# mainboard.net
KiCad netlist of a schematic drawn in EAGLE
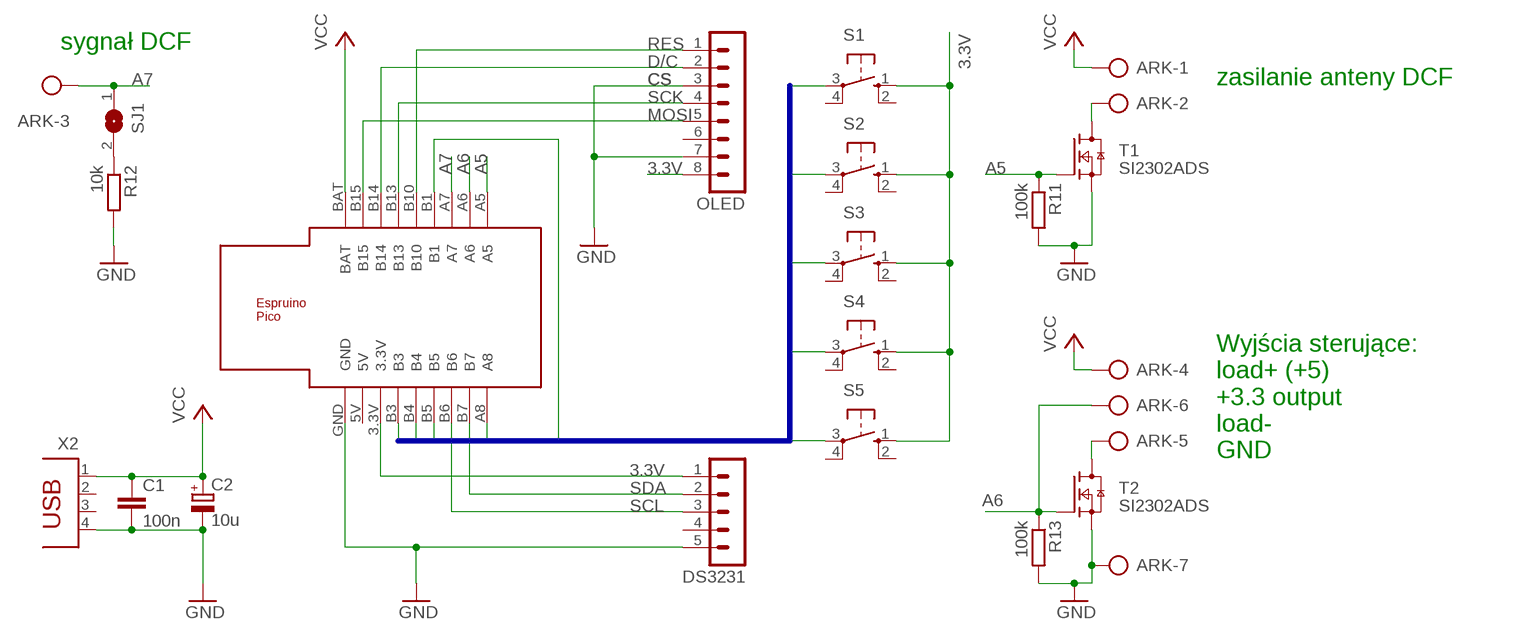
[diagram p0: schematic, sheet 1]

(export (version "E")
  (design (tool "Eeschema 10.0.6"))
  (components
    (comp (ref "ARK")
      (value "AK500/7")
      (footprint "eagle-import:AK500_7")
      (libsource (lib "eagle-import") (part "AK500/7"))
    )
    (comp (ref "C1")
      (value "100n")
      (footprint "eagle-import:C1206K")
      (libsource (lib "eagle-import") (part "C-EUC1206K"))
    )
    (comp (ref "C2")
      (value "10u")
      (footprint "eagle-import:A_3216-18W")
      (libsource (lib "eagle-import") (part "CPOL-EUA/3216-18W"))
    )
    (comp (ref "DS3231")
      (value "MA05-1")
      (footprint "eagle-import:MA05-1")
      (libsource (lib "eagle-import") (part "MA05-1"))
    )
    (comp (ref "OLED")
      (value "MA08-1")
      (footprint "eagle-import:MA08-1")
      (libsource (lib "eagle-import") (part "MA08-1"))
    )
    (comp (ref "R11")
      (value "100k")
      (footprint "eagle-import:M0805")
      (libsource (lib "eagle-import") (part "R-EU_M0805"))
    )
    (comp (ref "R12")
      (value "10k")
      (footprint "eagle-import:M0805")
      (libsource (lib "eagle-import") (part "R-EU_M0805"))
    )
    (comp (ref "R13")
      (value "100k")
      (footprint "eagle-import:M0805")
      (libsource (lib "eagle-import") (part "R-EU_M0805"))
    )
    (comp (ref "S1")
      (value "10-XX")
      (footprint "eagle-import:B3F-10XX")
      (fields (field (name "MPN") "B3F-1000"))
      (libsource (lib "eagle-import") (part "10-XX"))
    )
    (comp (ref "S2")
      (value "10-XX")
      (footprint "eagle-import:B3F-10XX")
      (fields (field (name "MPN") "B3F-1000"))
      (libsource (lib "eagle-import") (part "10-XX"))
    )
    (comp (ref "S3")
      (value "10-XX")
      (footprint "eagle-import:B3F-10XX")
      (fields (field (name "MPN") "B3F-1000"))
      (libsource (lib "eagle-import") (part "10-XX"))
    )
    (comp (ref "S4")
      (value "10-XX")
      (footprint "eagle-import:B3F-10XX")
      (fields (field (name "MPN") "B3F-1000"))
      (libsource (lib "eagle-import") (part "10-XX"))
    )
    (comp (ref "S5")
      (value "10-XX")
      (footprint "eagle-import:B3F-10XX")
      (fields (field (name "MPN") "B3F-1000"))
      (libsource (lib "eagle-import") (part "10-XX"))
    )
    (comp (ref "SJ1") (value "SJ") (footprint "eagle-import:SJ") (libsource (lib "eagle-import") (part "SJ")))
    (comp (ref "T1")
      (value "SI2302ADS")
      (footprint "eagle-import:SOT23")
      (libsource (lib "eagle-import") (part "2N7002E"))
    )
    (comp (ref "T2")
      (value "SI2302ADS")
      (footprint "eagle-import:SOT23")
      (libsource (lib "eagle-import") (part "2N7002E"))
    )
    (comp (ref "U$1")
      (value "ESPRUINO_PICO_0.1")
      (footprint "eagle-import:ESPRUINO_PICO_0.1")
      (libsource (lib "eagle-import") (part "ESPRUINO_PICO_0.1"))
    )
    (comp (ref "X2")
      (value "PN61729")
      (footprint "eagle-import:PN61729")
      (libsource (lib "eagle-import") (part "PN61729"))
    )
  )
  (nets
    (net (code "1") (name "/3.3V") (class "Default")
      (node (ref "DS3231") (pin "1") (pinfunction "1_1") (pintype "passive"))
      (node (ref "OLED") (pin "8") (pinfunction "8_8") (pintype "passive"))
      (node (ref "S1") (pin "1") (pinfunction "S_1") (pintype "passive"))
      (node (ref "S2") (pin "1") (pinfunction "S_1") (pintype "passive"))
      (node (ref "S3") (pin "1") (pinfunction "S_1") (pintype "passive"))
      (node (ref "S4") (pin "1") (pinfunction "S_1") (pintype "passive"))
      (node (ref "S5") (pin "1") (pinfunction "S_1") (pintype "passive"))
      (node (ref "U$1") (pin "3.3V") (pinfunction "3.3V_3.3V") (pintype "bidirectional"))
    )
    (net (code "2") (name "/A5") (class "Default")
      (node (ref "R11") (pin "1") (pinfunction "1_1") (pintype "passive"))
      (node (ref "T1") (pin "1") (pinfunction "G_1") (pintype "passive"))
      (node (ref "U$1") (pin "A5") (pinfunction "A5_A5") (pintype "bidirectional"))
    )
    (net (code "3") (name "/A6") (class "Default")
      (node (ref "ARK") (pin "6") (pinfunction "KL_6") (pintype "passive"))
      (node (ref "R13") (pin "1") (pinfunction "1_1") (pintype "passive"))
      (node (ref "T2") (pin "1") (pinfunction "G_1") (pintype "passive"))
      (node (ref "U$1") (pin "A6") (pinfunction "A6_A6") (pintype "bidirectional"))
    )
    (net (code "4") (name "/A7") (class "Default")
      (node (ref "ARK") (pin "3") (pinfunction "KL_3") (pintype "passive"))
      (node (ref "SJ1") (pin "1") (pinfunction "1_1") (pintype "passive"))
      (node (ref "U$1") (pin "A7") (pinfunction "A7_A7") (pintype "bidirectional"))
    )
    (net (code "5") (name "/D{slash}C") (class "Default")
      (node (ref "OLED") (pin "2") (pinfunction "2_2") (pintype "passive"))
      (node (ref "U$1") (pin "B14") (pinfunction "B14_B14") (pintype "bidirectional"))
    )
    (net (code "6") (name "/MOSI") (class "Default")
      (node (ref "OLED") (pin "5") (pinfunction "5_5") (pintype "passive"))
      (node (ref "U$1") (pin "B15") (pinfunction "B15_B15") (pintype "bidirectional"))
    )
    (net (code "7") (name "/RES") (class "Default")
      (node (ref "OLED") (pin "1") (pinfunction "1_1") (pintype "passive"))
      (node (ref "U$1") (pin "B10") (pinfunction "B10_B10") (pintype "bidirectional"))
    )
    (net (code "8") (name "/S1") (class "Default")
      (node (ref "S1") (pin "3") (pinfunction "P_3") (pintype "passive"))
      (node (ref "U$1") (pin "B3") (pinfunction "B3_B3") (pintype "bidirectional"))
    )
    (net (code "9") (name "/S2") (class "Default")
      (node (ref "S2") (pin "3") (pinfunction "P_3") (pintype "passive"))
      (node (ref "U$1") (pin "B4") (pinfunction "B4_B4") (pintype "bidirectional"))
    )
    (net (code "10") (name "/S3") (class "Default")
      (node (ref "S5") (pin "3") (pinfunction "P_3") (pintype "passive"))
      (node (ref "U$1") (pin "B5") (pinfunction "B5_B5") (pintype "bidirectional"))
    )
    (net (code "11") (name "/S4") (class "Default")
      (node (ref "S4") (pin "3") (pinfunction "P_3") (pintype "passive"))
      (node (ref "U$1") (pin "A8") (pinfunction "A8_A8") (pintype "bidirectional"))
    )
    (net (code "12") (name "/S5") (class "Default")
      (node (ref "S3") (pin "3") (pinfunction "P_3") (pintype "passive"))
      (node (ref "U$1") (pin "B1") (pinfunction "B1_B1") (pintype "bidirectional"))
    )
    (net (code "13") (name "/SCK") (class "Default")
      (node (ref "OLED") (pin "4") (pinfunction "4_4") (pintype "passive"))
      (node (ref "U$1") (pin "B13") (pinfunction "B13_B13") (pintype "bidirectional"))
    )
    (net (code "14") (name "/SCL") (class "Default")
      (node (ref "DS3231") (pin "3") (pinfunction "3_3") (pintype "passive"))
      (node (ref "U$1") (pin "B6") (pinfunction "B6_B6") (pintype "bidirectional"))
    )
    (net (code "15") (name "/SDA") (class "Default")
      (node (ref "DS3231") (pin "2") (pinfunction "2_2") (pintype "passive"))
      (node (ref "U$1") (pin "B7") (pinfunction "B7_B7") (pintype "bidirectional"))
    )
    (net (code "16") (name "GND") (class "Default")
      (node (ref "ARK") (pin "7") (pinfunction "KL_7") (pintype "passive"))
      (node (ref "C1") (pin "2") (pinfunction "2_2") (pintype "passive"))
      (node (ref "C2") (pin "-") (pinfunction "-_-") (pintype "passive"))
      (node (ref "DS3231") (pin "5") (pinfunction "5_5") (pintype "passive"))
      (node (ref "OLED") (pin "3") (pinfunction "3_3") (pintype "passive"))
      (node (ref "OLED") (pin "7") (pinfunction "7_7") (pintype "passive"))
      (node (ref "R11") (pin "2") (pinfunction "2_2") (pintype "passive"))
      (node (ref "R12") (pin "2") (pinfunction "2_2") (pintype "passive"))
      (node (ref "R13") (pin "2") (pinfunction "2_2") (pintype "passive"))
      (node (ref "T1") (pin "2") (pinfunction "S_2") (pintype "passive"))
      (node (ref "T2") (pin "2") (pinfunction "S_2") (pintype "passive"))
      (node (ref "U$1") (pin "GND") (pinfunction "GND_GND") (pintype "bidirectional"))
      (node (ref "X2") (pin "4") (pinfunction "4_4") (pintype "passive"))
    )
    (net (code "17") (name "Net-(ARKB-KL)") (class "Default")
      (node (ref "ARK") (pin "2") (pinfunction "KL_2") (pintype "passive"))
      (node (ref "T1") (pin "3") (pinfunction "D_3") (pintype "passive"))
    )
    (net (code "18") (name "Net-(ARKE-KL)") (class "Default")
      (node (ref "ARK") (pin "5") (pinfunction "KL_5") (pintype "passive"))
      (node (ref "T2") (pin "3") (pinfunction "D_3") (pintype "passive"))
    )
    (net (code "19") (name "Net-(R12-Pad1)") (class "Default")
      (node (ref "R12") (pin "1") (pinfunction "1_1") (pintype "passive"))
      (node (ref "SJ1") (pin "2") (pinfunction "2_2") (pintype "passive"))
    )
    (net (code "20") (name "VCC") (class "Default")
      (node (ref "ARK") (pin "1") (pinfunction "KL_1") (pintype "passive"))
      (node (ref "ARK") (pin "4") (pinfunction "KL_4") (pintype "passive"))
      (node (ref "C1") (pin "1") (pinfunction "1_1") (pintype "passive"))
      (node (ref "C2") (pin "+") (pinfunction "+_+") (pintype "passive"))
      (node (ref "U$1") (pin "BAT") (pinfunction "BAT_BAT") (pintype "bidirectional"))
      (node (ref "X2") (pin "1") (pinfunction "1_1") (pintype "passive"))
    )
    (net (code "21") (name "unconnected-(DS3231-Pad4)") (class "Default")
      (node (ref "DS3231") (pin "4") (pinfunction "4_4") (pintype "passive"))
    )
    (net (code "22") (name "unconnected-(OLED-Pad6)") (class "Default")
      (node (ref "OLED") (pin "6") (pinfunction "6_6") (pintype "passive"))
    )
    (net (code "23") (name "unconnected-(S1-P1-Pad4)") (class "Default")
      (node (ref "S1") (pin "4") (pinfunction "P1_4") (pintype "passive"))
    )
    (net (code "24") (name "unconnected-(S1-S1-Pad2)") (class "Default")
      (node (ref "S1") (pin "2") (pinfunction "S1_2") (pintype "passive"))
    )
    (net (code "25") (name "unconnected-(S2-P1-Pad4)") (class "Default")
      (node (ref "S2") (pin "4") (pinfunction "P1_4") (pintype "passive"))
    )
    (net (code "26") (name "unconnected-(S2-S1-Pad2)") (class "Default")
      (node (ref "S2") (pin "2") (pinfunction "S1_2") (pintype "passive"))
    )
    (net (code "27") (name "unconnected-(S3-P1-Pad4)") (class "Default")
      (node (ref "S3") (pin "4") (pinfunction "P1_4") (pintype "passive"))
    )
    (net (code "28") (name "unconnected-(S3-S1-Pad2)") (class "Default")
      (node (ref "S3") (pin "2") (pinfunction "S1_2") (pintype "passive"))
    )
    (net (code "29") (name "unconnected-(S4-P1-Pad4)") (class "Default")
      (node (ref "S4") (pin "4") (pinfunction "P1_4") (pintype "passive"))
    )
    (net (code "30") (name "unconnected-(S4-S1-Pad2)") (class "Default")
      (node (ref "S4") (pin "2") (pinfunction "S1_2") (pintype "passive"))
    )
    (net (code "31") (name "unconnected-(S5-P1-Pad4)") (class "Default")
      (node (ref "S5") (pin "4") (pinfunction "P1_4") (pintype "passive"))
    )
    (net (code "32") (name "unconnected-(S5-S1-Pad2)") (class "Default")
      (node (ref "S5") (pin "2") (pinfunction "S1_2") (pintype "passive"))
    )
    (net (code "33") (name "unconnected-(U$1-Pad5V)") (class "Default")
      (node (ref "U$1") (pin "5V") (pinfunction "5V_5V") (pintype "bidirectional"))
    )
    (net (code "34") (name "unconnected-(X2-Pad2)") (class "Default")
      (node (ref "X2") (pin "2") (pinfunction "2_2") (pintype "passive"))
    )
    (net (code "35") (name "unconnected-(X2-Pad3)") (class "Default")
      (node (ref "X2") (pin "3") (pinfunction "3_3") (pintype "passive"))
    )
  )
)
